# Peripherals.net
KiCad netlist of a schematic drawn in Altium Designer
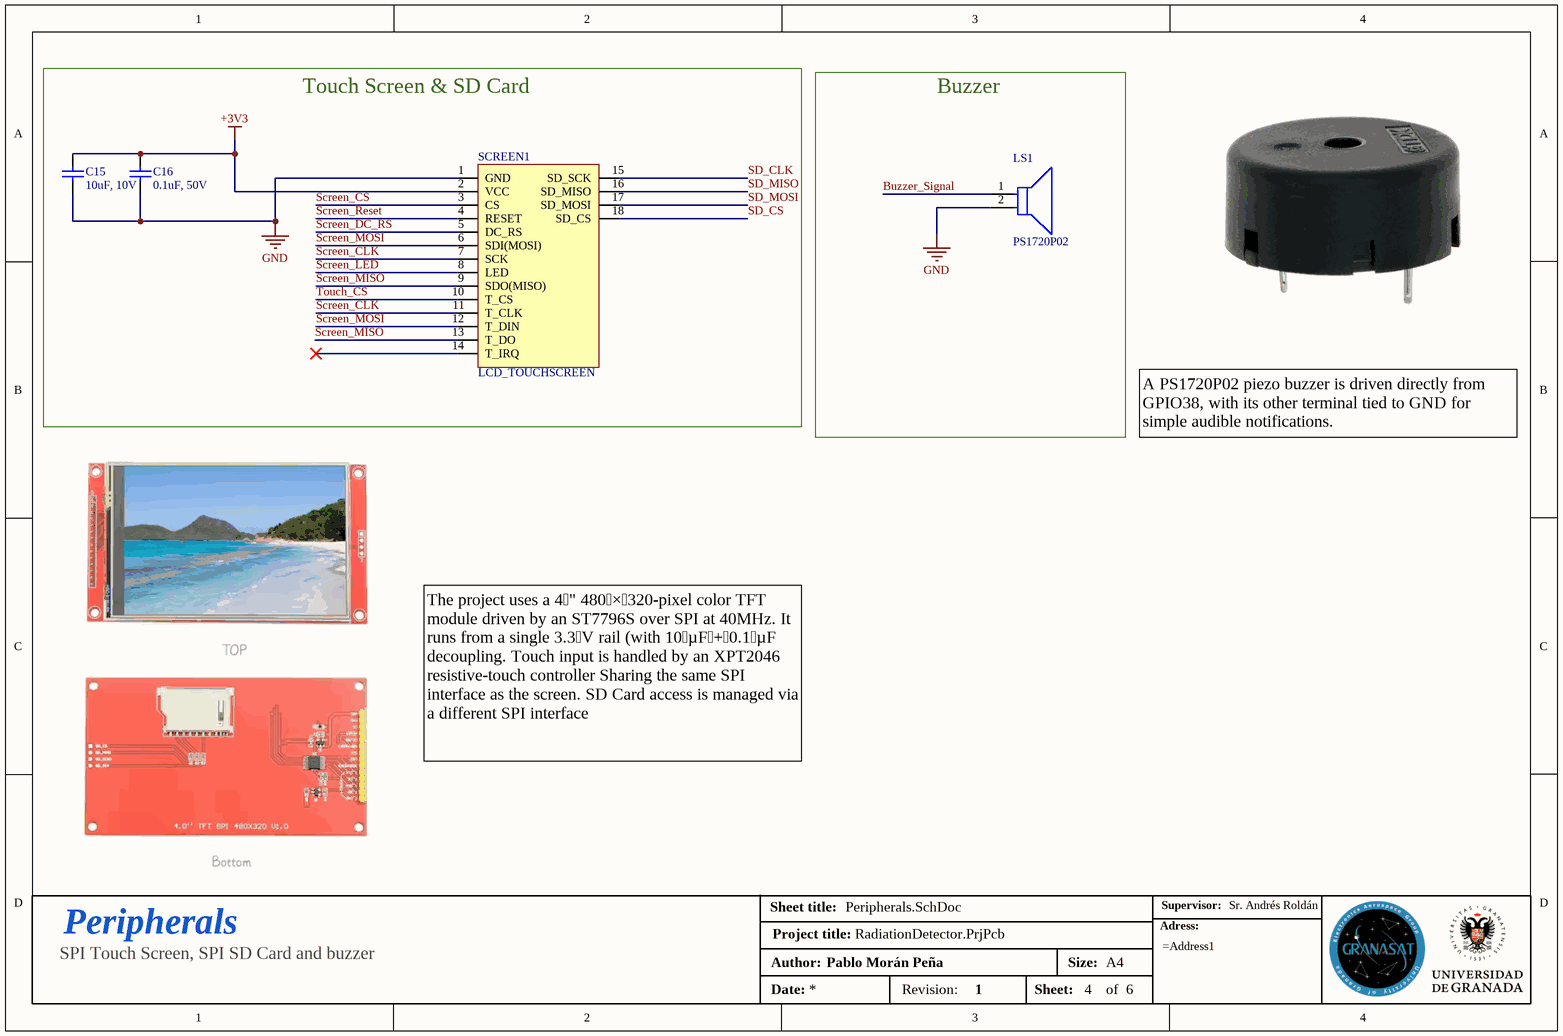
[diagram p0: Peripherals.SchDoc]

(export (version "E")
  (design (tool "Eeschema 10.0.6"))
  (components
    (comp (ref "C15")
      (value "10uF, 10V")
      (footprint "CAP 0402_1005")
      (description "CAP CER 10UF 10V X5R 0402")
      (fields
        (field (name "MANUFACTURER") "Samsung Electro-Mechanics")
        (field (name "MANUFACTURER PART NUMBER") "CL05A106MP8NUB8")
      )
      (libsource (lib "Schlib") (part "CL05A106MP8NUB8"))
    )
    (comp (ref "C16")
      (value "0.1uF, 50V")
      (footprint "CAP 0402_1005")
      (description "CAP CER 0.1UF 50V X7R 0402")
      (fields
        (field (name "MANUFACTURER") "Samsung")
        (field (name "MANUFACTURER PART NUMBER") "CL05B104KB5NNNC")
      )
      (libsource (lib "Schlib") (part "CL05B104KB5NNNC"))
    )
    (comp (ref "LS1")
      (value "PS1720P02")
      (footprint "FP-PS1720P02-MFG")
      (description "Data Line Filter, 1 Function(s)")
      (fields (field (name "LCSC PART NUMBER") "C96061"))
      (libsource (lib "Schlib") (part "PS1720P02"))
    )
    (comp (ref "SCREEN1")
      (value "LCD_TOUCHSCREEN")
      (footprint "LCD_TouchScreen")
      (description "Data Line Filter, 1 Function(s)")
      (fields (field (name "MANUFACTURER") "TDK") (field (name "MANUFACTURER PART NUMBER") "PS1720P02"))
      (libsource (lib "Schlib") (part "LCD_TOUCHSCREEN"))
    )
  )
  (nets
    (net (code "1") (name "+3V3") (class "Default")
      (node (ref "C15") (pin "2") (pinfunction "2_2") (pintype "passive"))
      (node (ref "C16") (pin "2") (pinfunction "2_2") (pintype "passive"))
      (node (ref "SCREEN1") (pin "2") (pinfunction "VCC_2") (pintype "passive"))
    )
    (net (code "2") (name "/Buzzer_Signal") (class "Default")
      (node (ref "LS1") (pin "1") (pinfunction "1_1") (pintype "passive"))
    )
    (net (code "3") (name "/SD_CLK") (class "Default")
      (node (ref "SCREEN1") (pin "15") (pinfunction "SD_SCK_15") (pintype "passive"))
    )
    (net (code "4") (name "/SD_CS") (class "Default")
      (node (ref "SCREEN1") (pin "18") (pinfunction "SD_CS_18") (pintype "passive"))
    )
    (net (code "5") (name "/SD_MISO") (class "Default")
      (node (ref "SCREEN1") (pin "16") (pinfunction "SD_MISO_16") (pintype "passive"))
    )
    (net (code "6") (name "/SD_MOSI") (class "Default")
      (node (ref "SCREEN1") (pin "17") (pinfunction "SD_MOSI_17") (pintype "passive"))
    )
    (net (code "7") (name "/Screen_CLK") (class "Default")
      (node (ref "SCREEN1") (pin "11") (pinfunction "T_CLK_11") (pintype "passive"))
      (node (ref "SCREEN1") (pin "7") (pinfunction "SCK_7") (pintype "passive"))
    )
    (net (code "8") (name "/Screen_CS") (class "Default")
      (node (ref "SCREEN1") (pin "3") (pinfunction "CS_3") (pintype "passive"))
    )
    (net (code "9") (name "/Screen_DC_RS") (class "Default")
      (node (ref "SCREEN1") (pin "5") (pinfunction "DC_RS_5") (pintype "passive"))
    )
    (net (code "10") (name "/Screen_LED") (class "Default")
      (node (ref "SCREEN1") (pin "8") (pinfunction "LED_8") (pintype "passive"))
    )
    (net (code "11") (name "/Screen_MISO") (class "Default")
      (node (ref "SCREEN1") (pin "13") (pinfunction "T_DO_13") (pintype "passive"))
      (node (ref "SCREEN1") (pin "9") (pinfunction "SDO(MISO)_9") (pintype "passive"))
    )
    (net (code "12") (name "/Screen_MOSI") (class "Default")
      (node (ref "SCREEN1") (pin "12") (pinfunction "T_DIN_12") (pintype "passive"))
      (node (ref "SCREEN1") (pin "6") (pinfunction "SDI(MOSI)_6") (pintype "passive"))
    )
    (net (code "13") (name "/Screen_Reset") (class "Default")
      (node (ref "SCREEN1") (pin "4") (pinfunction "RESET_4") (pintype "passive"))
    )
    (net (code "14") (name "/Touch_CS") (class "Default")
      (node (ref "SCREEN1") (pin "10") (pinfunction "T_CS_10") (pintype "passive"))
    )
    (net (code "15") (name "GND") (class "Default")
      (node (ref "C15") (pin "1") (pinfunction "1_1") (pintype "passive"))
      (node (ref "C16") (pin "1") (pinfunction "1_1") (pintype "passive"))
      (node (ref "LS1") (pin "2") (pinfunction "2_2") (pintype "passive"))
      (node (ref "SCREEN1") (pin "1") (pinfunction "GND_1") (pintype "passive"))
    )
    (net (code "16") (name "unconnected-(SCREEN1-T_IRQ-Pad14)") (class "Default")
      (node (ref "SCREEN1") (pin "14") (pinfunction "T_IRQ_14") (pintype "passive+no_connect"))
    )
  )
)
